# SCH_Smart_Door_Quach_Trung_an.net
KiCad netlist of a schematic drawn in Altium Designer
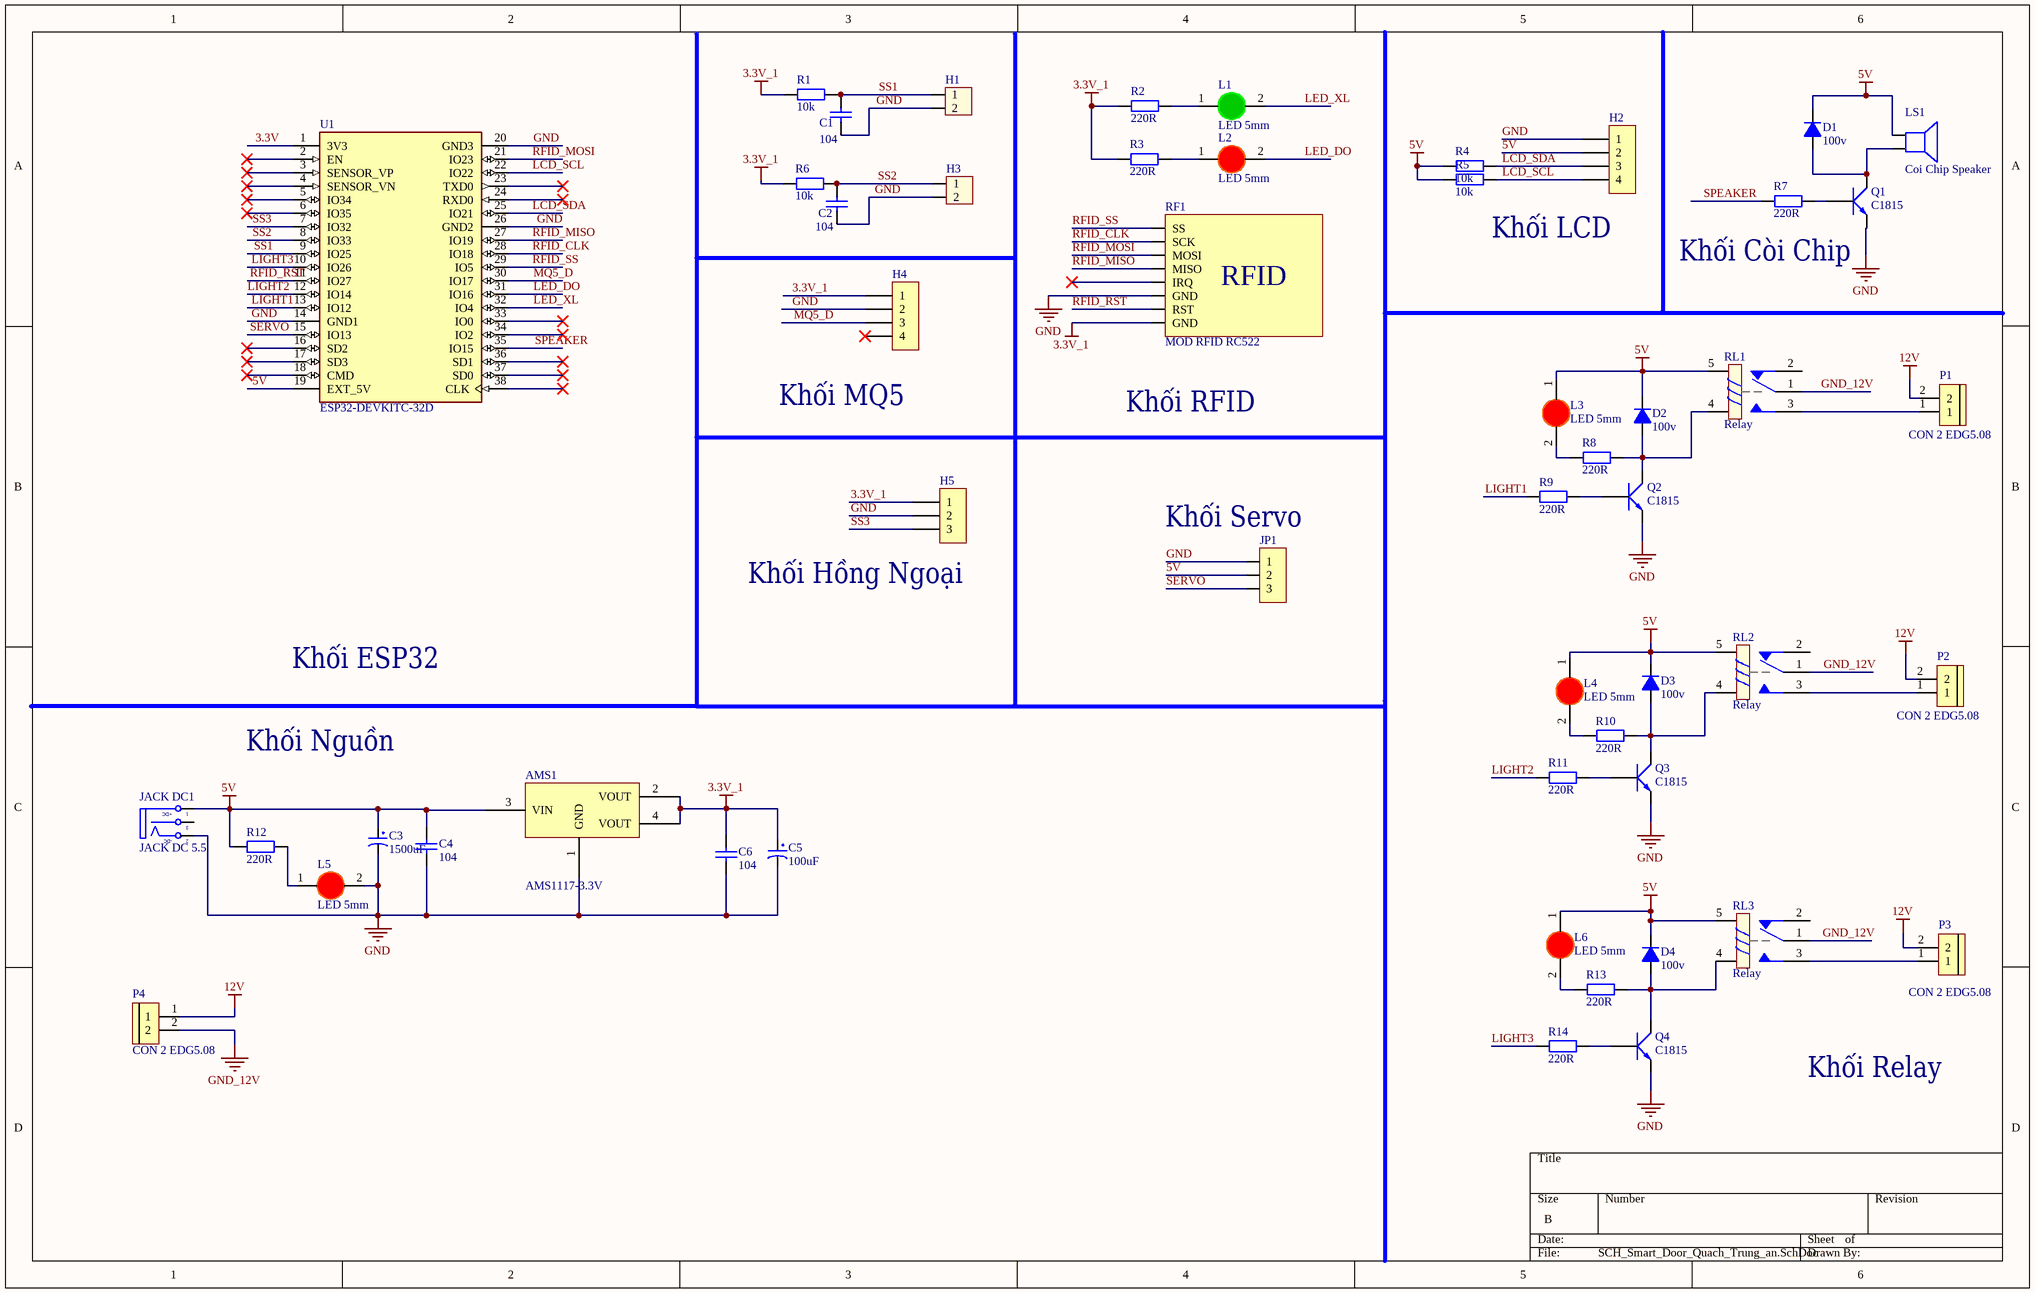
[diagram p0: SCH_Smart_Door_Quach_Trung_an.SchDoc]

(export (version "E")
  (design (tool "Eeschema 10.0.6"))
  (components
    (comp (ref "AMS1")
      (value "AMS1117-3.3V")
      (footprint "SOT223")
      (description "Dán")
      (libsource (lib "Altium_Lib_by_KhueNguyenCreator") (part "AMS1117 SMD"))
    )
    (comp (ref "C1")
      (value "104")
      (footprint "tu gom")
      (description "Cắm")
      (libsource (lib "Altium_Lib_by_KhueNguyenCreator") (part "Tu gom 104 50V"))
    )
    (comp (ref "C2")
      (value "104")
      (footprint "tu gom")
      (description "Cắm")
      (libsource (lib "Altium_Lib_by_KhueNguyenCreator") (part "Tu gom 104 50V"))
    )
    (comp (ref "C3")
      (value "1500uF")
      (footprint "tu hoa 10mm")
      (description "Cắm")
      (libsource (lib "Altium_Lib_by_KhueNguyenCreator") (part "Tu Hoa 1500uF 16V 10x20"))
    )
    (comp (ref "C4")
      (value "104")
      (footprint "tu gom")
      (description "Cắm")
      (libsource (lib "Altium_Lib_by_KhueNguyenCreator") (part "Tu gom 104 50V"))
    )
    (comp (ref "C5")
      (value "100uF")
      (footprint "tu hoa 5mm")
      (description "Cắm")
      (libsource (lib "Altium_Lib_by_KhueNguyenCreator") (part "Tu Hoa 100uF 16V 5x7"))
    )
    (comp (ref "C6")
      (value "104")
      (footprint "tu gom")
      (description "Cắm")
      (libsource (lib "Altium_Lib_by_KhueNguyenCreator") (part "Tu gom 104 50V"))
    )
    (comp (ref "D1")
      (value "100v")
      (footprint "DIODE 1A")
      (description "Cắm")
      (libsource (lib "Altium_Lib_by_KhueNguyenCreator") (part "Diode 1N4007"))
    )
    (comp (ref "D2")
      (value "100v")
      (footprint "DIODE 1A")
      (description "Cắm")
      (libsource (lib "Altium_Lib_by_KhueNguyenCreator") (part "Diode 1N4007"))
    )
    (comp (ref "D3")
      (value "100v")
      (footprint "DIODE 1A")
      (description "Cắm")
      (libsource (lib "Altium_Lib_by_KhueNguyenCreator") (part "Diode 1N4007"))
    )
    (comp (ref "D4")
      (value "100v")
      (footprint "DIODE 1A")
      (description "Cắm")
      (libsource (lib "Altium_Lib_by_KhueNguyenCreator") (part "Diode 1N4007"))
    )
    (comp (ref "H1")
      (value "Header 2P 2.54 Duc Cong")
      (footprint "Header 2P DC 2.54")
      (description "Cắm")
      (libsource (lib "Altium_Lib_by_KhueNguyenCreator") (part "Header 2P 2.54 Duc Cong"))
    )
    (comp (ref "H2")
      (value "Header 4P 2.54 Duc Cong")
      (footprint "Header 4P DC 2.54")
      (description "Cắm")
      (libsource (lib "Altium_Lib_by_KhueNguyenCreator") (part "Header 4P 2.54 Duc Cong"))
    )
    (comp (ref "H3")
      (value "Header 2P 2.54 Duc Cong")
      (footprint "Header 2P DC 2.54")
      (description "Cắm")
      (libsource (lib "Altium_Lib_by_KhueNguyenCreator") (part "Header 2P 2.54 Duc Cong"))
    )
    (comp (ref "H4")
      (value "Header 4P 2.54 Duc Cong")
      (footprint "Header 4P DC 2.54")
      (description "Cắm")
      (libsource (lib "Altium_Lib_by_KhueNguyenCreator") (part "Header 4P 2.54 Duc Cong"))
    )
    (comp (ref "H5")
      (value "Header 3P 2.54 Duc Cong")
      (footprint "Header 3P DC 2.54")
      (description "Cắm")
      (libsource (lib "Altium_Lib_by_KhueNguyenCreator") (part "Header 3P 2.54 Duc Cong"))
    )
    (comp (ref "JACK DC1")
      (value "JACK DC 5.5")
      (footprint "JACK DC 5.5")
      (libsource (lib "Altium_Lib_by_KhueNguyenCreator") (part "JACK DC 5.5"))
    )
    (comp (ref "JP1")
      (value "JP 1x3 2.54")
      (footprint "JP 1x3 DC")
      (description "Cắm")
      (libsource (lib "Altium_Lib_by_KhueNguyenCreator") (part "JP 1x3 2.54 Duc Cong"))
    )
    (comp (ref "L1")
      (value "LED 5mm")
      (footprint "LED-5MM-Green")
      (description "Cắm")
      (libsource (lib "Altium_Lib_by_KhueNguyenCreator") (part "LED 5mm Xanh La"))
    )
    (comp (ref "L2")
      (value "LED 5mm")
      (footprint "LED-5MM-RED")
      (description "Cắm")
      (libsource (lib "Altium_Lib_by_KhueNguyenCreator") (part "LED 5mm Do"))
    )
    (comp (ref "L3")
      (value "LED 5mm")
      (footprint "LED-5MM-RED")
      (description "Cắm")
      (libsource (lib "Altium_Lib_by_KhueNguyenCreator") (part "LED 5mm Do"))
    )
    (comp (ref "L4")
      (value "LED 5mm")
      (footprint "LED-5MM-RED")
      (description "Cắm")
      (libsource (lib "Altium_Lib_by_KhueNguyenCreator") (part "LED 5mm Do"))
    )
    (comp (ref "L5")
      (value "LED 5mm")
      (footprint "LED-5MM-RED")
      (description "Cắm")
      (libsource (lib "Altium_Lib_by_KhueNguyenCreator") (part "LED 5mm Do"))
    )
    (comp (ref "L6")
      (value "LED 5mm")
      (footprint "LED-5MM-RED")
      (description "Cắm")
      (libsource (lib "Altium_Lib_by_KhueNguyenCreator") (part "LED 5mm Do"))
    )
    (comp (ref "LS1")
      (value "Coi Chip Speaker")
      (footprint "Coi Chip Speacker")
      (description "Còi chip")
      (libsource (lib "Altium_Lib_by_KhueNguyenCreator") (part "Coi Chip Speaker"))
    )
    (comp (ref "P1")
      (value "CON 2 EDG5.08")
      (footprint "CON 2 2EDG5.08")
      (description "Cắm")
      (libsource (lib "Altium_Lib_by_KhueNguyenCreator") (part "CON 2 EDG5.08"))
    )
    (comp (ref "P2")
      (value "CON 2 EDG5.08")
      (footprint "CON 2 2EDG5.08")
      (description "Cắm")
      (libsource (lib "Altium_Lib_by_KhueNguyenCreator") (part "CON 2 EDG5.08"))
    )
    (comp (ref "P3")
      (value "CON 2 EDG5.08")
      (footprint "CON 2 2EDG5.08")
      (description "Cắm")
      (libsource (lib "Altium_Lib_by_KhueNguyenCreator") (part "CON 2 EDG5.08"))
    )
    (comp (ref "P4")
      (value "CON 2 EDG5.08")
      (footprint "CON 2 2EDG5.08")
      (description "Cắm")
      (libsource (lib "") (part "CON 2 EDG5.08_1"))
    )
    (comp (ref "Q1")
      (value "C1815")
      (footprint "TO92")
      (description "NPN transistor")
      (libsource (lib "Altium_Lib_by_KhueNguyenCreator") (part "C1815"))
    )
    (comp (ref "Q2")
      (value "C1815")
      (footprint "TO92")
      (description "NPN transistor")
      (libsource (lib "Altium_Lib_by_KhueNguyenCreator") (part "C1815"))
    )
    (comp (ref "Q3")
      (value "C1815")
      (footprint "TO92")
      (description "NPN transistor")
      (libsource (lib "Altium_Lib_by_KhueNguyenCreator") (part "C1815"))
    )
    (comp (ref "Q4")
      (value "C1815")
      (footprint "TO92")
      (description "NPN transistor")
      (libsource (lib "Altium_Lib_by_KhueNguyenCreator") (part "C1815"))
    )
    (comp (ref "R1")
      (value "10k")
      (footprint "tro vach 1/4w")
      (description "Căm")
      (libsource (lib "Altium_Lib_by_KhueNguyenCreator") (part "Tro Vach 1/4W 5% 10k"))
    )
    (comp (ref "R2")
      (value "220R")
      (footprint "tro vach 1/4w")
      (description "Cắm")
      (libsource (lib "Altium_Lib_by_KhueNguyenCreator") (part "Tro Vach 1/4W 5% 220R"))
    )
    (comp (ref "R3")
      (value "220R")
      (footprint "tro vach 1/4w")
      (description "Cắm")
      (libsource (lib "Altium_Lib_by_KhueNguyenCreator") (part "Tro Vach 1/4W 5% 220R"))
    )
    (comp (ref "R4")
      (value "10k")
      (footprint "tro vach 1/4w")
      (description "Căm")
      (libsource (lib "Altium_Lib_by_KhueNguyenCreator") (part "Tro Vach 1/4W 5% 10k"))
    )
    (comp (ref "R5")
      (value "10k")
      (footprint "tro vach 1/4w")
      (description "Căm")
      (libsource (lib "Altium_Lib_by_KhueNguyenCreator") (part "Tro Vach 1/4W 5% 10k"))
    )
    (comp (ref "R6")
      (value "10k")
      (footprint "tro vach 1/4w")
      (description "Căm")
      (libsource (lib "Altium_Lib_by_KhueNguyenCreator") (part "Tro Vach 1/4W 5% 10k"))
    )
    (comp (ref "R7")
      (value "220R")
      (footprint "tro vach 1/4w")
      (description "Cắm")
      (libsource (lib "Altium_Lib_by_KhueNguyenCreator") (part "Tro Vach 1/4W 5% 220R"))
    )
    (comp (ref "R8")
      (value "220R")
      (footprint "tro vach 1/4w")
      (description "Cắm")
      (libsource (lib "Altium_Lib_by_KhueNguyenCreator") (part "Tro Vach 1/4W 5% 220R"))
    )
    (comp (ref "R9")
      (value "220R")
      (footprint "tro vach 1/4w")
      (description "Cắm")
      (libsource (lib "Altium_Lib_by_KhueNguyenCreator") (part "Tro Vach 1/4W 5% 220R"))
    )
    (comp (ref "R10")
      (value "220R")
      (footprint "tro vach 1/4w")
      (description "Cắm")
      (libsource (lib "Altium_Lib_by_KhueNguyenCreator") (part "Tro Vach 1/4W 5% 220R"))
    )
    (comp (ref "R11")
      (value "220R")
      (footprint "tro vach 1/4w")
      (description "Cắm")
      (libsource (lib "Altium_Lib_by_KhueNguyenCreator") (part "Tro Vach 1/4W 5% 220R"))
    )
    (comp (ref "R12")
      (value "220R")
      (footprint "tro vach 1/4w")
      (description "Cắm")
      (libsource (lib "Altium_Lib_by_KhueNguyenCreator") (part "Tro Vach 1/4W 5% 220R"))
    )
    (comp (ref "R13")
      (value "220R")
      (footprint "tro vach 1/4w")
      (description "Cắm")
      (libsource (lib "Altium_Lib_by_KhueNguyenCreator") (part "Tro Vach 1/4W 5% 220R"))
    )
    (comp (ref "R14")
      (value "220R")
      (footprint "tro vach 1/4w")
      (description "Cắm")
      (libsource (lib "Altium_Lib_by_KhueNguyenCreator") (part "Tro Vach 1/4W 5% 220R"))
    )
    (comp (ref "RF1")
      (value "MOD RFID RC522")
      (footprint "MOD RFID RC522")
      (libsource (lib "Altium_Lib_by_KhueNguyenCreator") (part "MOD RFID RC522"))
    )
    (comp (ref "RL1")
      (value "Relay")
      (footprint "Relay 5 Chan SRD")
      (description "Relay 5 Chan")
      (libsource (lib "Altium_Lib_by_KhueNguyenCreator") (part "Relay 5 Chan SRD"))
    )
    (comp (ref "RL2")
      (value "Relay")
      (footprint "Relay 5 Chan SRD")
      (description "Relay 5 Chan")
      (libsource (lib "Altium_Lib_by_KhueNguyenCreator") (part "Relay 5 Chan SRD"))
    )
    (comp (ref "RL3")
      (value "Relay")
      (footprint "Relay 5 Chan SRD")
      (description "Relay 5 Chan")
      (libsource (lib "Altium_Lib_by_KhueNguyenCreator") (part "Relay 5 Chan SRD"))
    )
    (comp (ref "U1")
      (value "ESP32-DEVKITC-32D")
      (footprint "MODULE_ESP32-DEVKITC-32D")
      (description "EVAL BOARD FOR ESP-WROOM-32")
      (fields (field (name "MF") "Espressif Systems"))
      (libsource (lib "Altium_Lib_by_KhueNguyenCreator") (part "ESP32-DEVKITC-32D"))
    )
  )
  (nets
    (net (code "1") (name "/3.3V") (class "Default")
      (node (ref "U1") (pin "1") (pinfunction "3V3_1") (pintype "power_in"))
    )
    (net (code "2") (name "/LCD_SCL") (class "Default")
      (node (ref "H2") (pin "4") (pinfunction "4_4") (pintype "passive"))
      (node (ref "R5") (pin "2") (pinfunction "2_2") (pintype "passive"))
      (node (ref "U1") (pin "22") (pinfunction "IO22_22") (pintype "bidirectional"))
    )
    (net (code "3") (name "/LCD_SDA") (class "Default")
      (node (ref "H2") (pin "3") (pinfunction "3_3") (pintype "passive"))
      (node (ref "R4") (pin "2") (pinfunction "2_2") (pintype "passive"))
      (node (ref "U1") (pin "25") (pinfunction "IO21_25") (pintype "bidirectional"))
    )
    (net (code "4") (name "/LED_DO") (class "Default")
      (node (ref "L2") (pin "2") (pinfunction "K_2") (pintype "passive"))
      (node (ref "U1") (pin "31") (pinfunction "IO16_31") (pintype "bidirectional"))
    )
    (net (code "5") (name "/LED_XL") (class "Default")
      (node (ref "L1") (pin "2") (pinfunction "K_2") (pintype "passive"))
      (node (ref "U1") (pin "32") (pinfunction "IO4_32") (pintype "bidirectional"))
    )
    (net (code "6") (name "/LIGHT1") (class "Default")
      (node (ref "R9") (pin "1") (pinfunction "1_1") (pintype "passive"))
      (node (ref "U1") (pin "13") (pinfunction "IO12_13") (pintype "bidirectional"))
    )
    (net (code "7") (name "/LIGHT2") (class "Default")
      (node (ref "R11") (pin "1") (pinfunction "1_1") (pintype "passive"))
      (node (ref "U1") (pin "12") (pinfunction "IO14_12") (pintype "bidirectional"))
    )
    (net (code "8") (name "/LIGHT3") (class "Default")
      (node (ref "R14") (pin "1") (pinfunction "1_1") (pintype "passive"))
      (node (ref "U1") (pin "10") (pinfunction "IO26_10") (pintype "bidirectional"))
    )
    (net (code "9") (name "/MQ5_D") (class "Default")
      (node (ref "H4") (pin "3") (pinfunction "3_3") (pintype "passive"))
      (node (ref "U1") (pin "30") (pinfunction "IO17_30") (pintype "bidirectional"))
    )
    (net (code "10") (name "/RFID_CLK") (class "Default")
      (node (ref "RF1") (pin "2") (pinfunction "SCK_2") (pintype "passive"))
      (node (ref "U1") (pin "28") (pinfunction "IO18_28") (pintype "bidirectional"))
    )
    (net (code "11") (name "/RFID_MISO") (class "Default")
      (node (ref "RF1") (pin "4") (pinfunction "MISO_4") (pintype "passive"))
      (node (ref "U1") (pin "27") (pinfunction "IO19_27") (pintype "bidirectional"))
    )
    (net (code "12") (name "/RFID_MOSI") (class "Default")
      (node (ref "RF1") (pin "3") (pinfunction "MOSI_3") (pintype "passive"))
      (node (ref "U1") (pin "21") (pinfunction "IO23_21") (pintype "bidirectional"))
    )
    (net (code "13") (name "/RFID_RST") (class "Default")
      (node (ref "RF1") (pin "7") (pinfunction "RST_7") (pintype "passive"))
      (node (ref "U1") (pin "11") (pinfunction "IO27_11") (pintype "bidirectional"))
    )
    (net (code "14") (name "/RFID_SS") (class "Default")
      (node (ref "RF1") (pin "1") (pinfunction "SS_1") (pintype "passive"))
      (node (ref "U1") (pin "29") (pinfunction "IO5_29") (pintype "bidirectional"))
    )
    (net (code "15") (name "/SERVO") (class "Default")
      (node (ref "JP1") (pin "3") (pinfunction "3_3") (pintype "passive"))
      (node (ref "U1") (pin "15") (pinfunction "IO13_15") (pintype "bidirectional"))
    )
    (net (code "16") (name "/SPEAKER") (class "Default")
      (node (ref "R7") (pin "1") (pinfunction "1_1") (pintype "passive"))
      (node (ref "U1") (pin "35") (pinfunction "IO15_35") (pintype "bidirectional"))
    )
    (net (code "17") (name "/SS1") (class "Default")
      (node (ref "C1") (pin "1") (pinfunction "1_1") (pintype "passive"))
      (node (ref "H1") (pin "1") (pinfunction "1_1") (pintype "passive"))
      (node (ref "R1") (pin "2") (pinfunction "2_2") (pintype "passive"))
      (node (ref "U1") (pin "9") (pinfunction "IO25_9") (pintype "bidirectional"))
    )
    (net (code "18") (name "/SS2") (class "Default")
      (node (ref "C2") (pin "1") (pinfunction "1_1") (pintype "passive"))
      (node (ref "H3") (pin "1") (pinfunction "1_1") (pintype "passive"))
      (node (ref "R6") (pin "2") (pinfunction "2_2") (pintype "passive"))
      (node (ref "U1") (pin "8") (pinfunction "IO33_8") (pintype "bidirectional"))
    )
    (net (code "19") (name "/SS3") (class "Default")
      (node (ref "H5") (pin "3") (pinfunction "3_3") (pintype "passive"))
      (node (ref "U1") (pin "7") (pinfunction "IO32_7") (pintype "bidirectional"))
    )
    (net (code "20") (name "3.3V_1") (class "Default")
      (node (ref "AMS1") (pin "2") (pinfunction "VOUT_2") (pintype "passive"))
      (node (ref "AMS1") (pin "4") (pinfunction "VOUT_4") (pintype "passive"))
      (node (ref "C5") (pin "1") (pinfunction "1_1") (pintype "passive"))
      (node (ref "C6") (pin "1") (pinfunction "1_1") (pintype "passive"))
      (node (ref "H4") (pin "1") (pinfunction "1_1") (pintype "passive"))
      (node (ref "H5") (pin "1") (pinfunction "1_1") (pintype "passive"))
      (node (ref "R1") (pin "1") (pinfunction "1_1") (pintype "passive"))
      (node (ref "R2") (pin "1") (pinfunction "1_1") (pintype "passive"))
      (node (ref "R3") (pin "1") (pinfunction "1_1") (pintype "passive"))
      (node (ref "R6") (pin "1") (pinfunction "1_1") (pintype "passive"))
      (node (ref "RF1") (pin "8") (pinfunction "GND_8") (pintype "passive"))
    )
    (net (code "21") (name "5V") (class "Default")
      (node (ref "AMS1") (pin "3") (pinfunction "VIN_3") (pintype "passive"))
      (node (ref "C3") (pin "1") (pinfunction "1_1") (pintype "passive"))
      (node (ref "C4") (pin "1") (pinfunction "1_1") (pintype "passive"))
      (node (ref "D1") (pin "2") (pinfunction "K_2") (pintype "passive"))
      (node (ref "D2") (pin "2") (pinfunction "K_2") (pintype "passive"))
      (node (ref "D3") (pin "2") (pinfunction "K_2") (pintype "passive"))
      (node (ref "D4") (pin "2") (pinfunction "K_2") (pintype "passive"))
      (node (ref "H2") (pin "2") (pinfunction "2_2") (pintype "passive"))
      (node (ref "JACK DC1") (pin "1") (pinfunction "T_1") (pintype "passive"))
      (node (ref "JP1") (pin "2") (pinfunction "2_2") (pintype "passive"))
      (node (ref "L3") (pin "1") (pinfunction "A_1") (pintype "passive"))
      (node (ref "L4") (pin "1") (pinfunction "A_1") (pintype "passive"))
      (node (ref "L6") (pin "1") (pinfunction "A_1") (pintype "passive"))
      (node (ref "LS1") (pin "1") (pinfunction "1_1") (pintype "passive"))
      (node (ref "R12") (pin "1") (pinfunction "1_1") (pintype "passive"))
      (node (ref "R4") (pin "1") (pinfunction "1_1") (pintype "passive"))
      (node (ref "R5") (pin "1") (pinfunction "1_1") (pintype "passive"))
      (node (ref "RL1") (pin "5") (pinfunction "5_5") (pintype "passive"))
      (node (ref "RL2") (pin "5") (pinfunction "5_5") (pintype "passive"))
      (node (ref "RL3") (pin "5") (pinfunction "5_5") (pintype "passive"))
      (node (ref "U1") (pin "19") (pinfunction "EXT_5V_19") (pintype "power_in"))
    )
    (net (code "22") (name "12V") (class "Default")
      (node (ref "P1") (pin "2") (pinfunction "2_2") (pintype "passive"))
      (node (ref "P2") (pin "2") (pinfunction "2_2") (pintype "passive"))
      (node (ref "P3") (pin "2") (pinfunction "2_2") (pintype "passive"))
      (node (ref "P4") (pin "1") (pinfunction "1_1") (pintype "passive"))
    )
    (net (code "23") (name "GND") (class "Default")
      (node (ref "AMS1") (pin "1") (pinfunction "GND_1") (pintype "passive"))
      (node (ref "C1") (pin "2") (pinfunction "2_2") (pintype "passive"))
      (node (ref "C2") (pin "2") (pinfunction "2_2") (pintype "passive"))
      (node (ref "C3") (pin "2") (pinfunction "2_2") (pintype "passive"))
      (node (ref "C4") (pin "2") (pinfunction "2_2") (pintype "passive"))
      (node (ref "C5") (pin "2") (pinfunction "2_2") (pintype "passive"))
      (node (ref "C6") (pin "2") (pinfunction "2_2") (pintype "passive"))
      (node (ref "H1") (pin "2") (pinfunction "2_2") (pintype "passive"))
      (node (ref "H2") (pin "1") (pinfunction "1_1") (pintype "passive"))
      (node (ref "H3") (pin "2") (pinfunction "2_2") (pintype "passive"))
      (node (ref "H4") (pin "2") (pinfunction "2_2") (pintype "passive"))
      (node (ref "H5") (pin "2") (pinfunction "2_2") (pintype "passive"))
      (node (ref "JACK DC1") (pin "2") (pinfunction "TN_2") (pintype "passive"))
      (node (ref "JP1") (pin "1") (pinfunction "1_1") (pintype "passive"))
      (node (ref "L5") (pin "2") (pinfunction "K_2") (pintype "passive"))
      (node (ref "Q1") (pin "1") (pinfunction "E_1") (pintype "passive"))
      (node (ref "Q2") (pin "1") (pinfunction "E_1") (pintype "passive"))
      (node (ref "Q3") (pin "1") (pinfunction "E_1") (pintype "passive"))
      (node (ref "Q4") (pin "1") (pinfunction "E_1") (pintype "passive"))
      (node (ref "RF1") (pin "6") (pinfunction "GND_6") (pintype "passive"))
      (node (ref "U1") (pin "14") (pinfunction "GND1_14") (pintype "power_in"))
      (node (ref "U1") (pin "20") (pinfunction "GND3_20") (pintype "power_in"))
      (node (ref "U1") (pin "26") (pinfunction "GND2_26") (pintype "power_in"))
    )
    (net (code "24") (name "GND_12V") (class "Default")
      (node (ref "P4") (pin "2") (pinfunction "2_2") (pintype "passive"))
      (node (ref "RL1") (pin "1") (pinfunction "1_1") (pintype "passive"))
      (node (ref "RL2") (pin "1") (pinfunction "1_1") (pintype "passive"))
      (node (ref "RL3") (pin "1") (pinfunction "1_1") (pintype "passive"))
    )
    (net (code "25") (name "Net-(D1-A)") (class "Default")
      (node (ref "D1") (pin "1") (pinfunction "A_1") (pintype "passive"))
      (node (ref "LS1") (pin "2") (pinfunction "2_2") (pintype "passive"))
      (node (ref "Q1") (pin "2") (pinfunction "C_2") (pintype "passive"))
    )
    (net (code "26") (name "Net-(D2-A)") (class "Default")
      (node (ref "D2") (pin "1") (pinfunction "A_1") (pintype "passive"))
      (node (ref "Q2") (pin "2") (pinfunction "C_2") (pintype "passive"))
      (node (ref "R8") (pin "1") (pinfunction "1_1") (pintype "passive"))
      (node (ref "RL1") (pin "4") (pinfunction "4_4") (pintype "passive"))
    )
    (net (code "27") (name "Net-(D3-A)") (class "Default")
      (node (ref "D3") (pin "1") (pinfunction "A_1") (pintype "passive"))
      (node (ref "Q3") (pin "2") (pinfunction "C_2") (pintype "passive"))
      (node (ref "R10") (pin "1") (pinfunction "1_1") (pintype "passive"))
      (node (ref "RL2") (pin "4") (pinfunction "4_4") (pintype "passive"))
    )
    (net (code "28") (name "Net-(D4-A)") (class "Default")
      (node (ref "D4") (pin "1") (pinfunction "A_1") (pintype "passive"))
      (node (ref "Q4") (pin "2") (pinfunction "C_2") (pintype "passive"))
      (node (ref "R13") (pin "1") (pinfunction "1_1") (pintype "passive"))
      (node (ref "RL3") (pin "4") (pinfunction "4_4") (pintype "passive"))
    )
    (net (code "29") (name "Net-(L1-A)") (class "Default")
      (node (ref "L1") (pin "1") (pinfunction "A_1") (pintype "passive"))
      (node (ref "R2") (pin "2") (pinfunction "2_2") (pintype "passive"))
    )
    (net (code "30") (name "Net-(L2-A)") (class "Default")
      (node (ref "L2") (pin "1") (pinfunction "A_1") (pintype "passive"))
      (node (ref "R3") (pin "2") (pinfunction "2_2") (pintype "passive"))
    )
    (net (code "31") (name "Net-(L3-K)") (class "Default")
      (node (ref "L3") (pin "2") (pinfunction "K_2") (pintype "passive"))
      (node (ref "R8") (pin "2") (pinfunction "2_2") (pintype "passive"))
    )
    (net (code "32") (name "Net-(L4-K)") (class "Default")
      (node (ref "L4") (pin "2") (pinfunction "K_2") (pintype "passive"))
      (node (ref "R10") (pin "2") (pinfunction "2_2") (pintype "passive"))
    )
    (net (code "33") (name "Net-(L5-A)") (class "Default")
      (node (ref "L5") (pin "1") (pinfunction "A_1") (pintype "passive"))
      (node (ref "R12") (pin "2") (pinfunction "2_2") (pintype "passive"))
    )
    (net (code "34") (name "Net-(L6-K)") (class "Default")
      (node (ref "L6") (pin "2") (pinfunction "K_2") (pintype "passive"))
      (node (ref "R13") (pin "2") (pinfunction "2_2") (pintype "passive"))
    )
    (net (code "35") (name "Net-(P1-Pad1)") (class "Default")
      (node (ref "P1") (pin "1") (pinfunction "1_1") (pintype "passive"))
      (node (ref "RL1") (pin "3") (pinfunction "3_3") (pintype "passive"))
    )
    (net (code "36") (name "Net-(P2-Pad1)") (class "Default")
      (node (ref "P2") (pin "1") (pinfunction "1_1") (pintype "passive"))
      (node (ref "RL2") (pin "3") (pinfunction "3_3") (pintype "passive"))
    )
    (net (code "37") (name "Net-(P3-Pad1)") (class "Default")
      (node (ref "P3") (pin "1") (pinfunction "1_1") (pintype "passive"))
      (node (ref "RL3") (pin "3") (pinfunction "3_3") (pintype "passive"))
    )
    (net (code "38") (name "Net-(Q1-B)") (class "Default")
      (node (ref "Q1") (pin "3") (pinfunction "B_3") (pintype "passive"))
      (node (ref "R7") (pin "2") (pinfunction "2_2") (pintype "passive"))
    )
    (net (code "39") (name "Net-(Q2-B)") (class "Default")
      (node (ref "Q2") (pin "3") (pinfunction "B_3") (pintype "passive"))
      (node (ref "R9") (pin "2") (pinfunction "2_2") (pintype "passive"))
    )
    (net (code "40") (name "Net-(Q3-B)") (class "Default")
      (node (ref "Q3") (pin "3") (pinfunction "B_3") (pintype "passive"))
      (node (ref "R11") (pin "2") (pinfunction "2_2") (pintype "passive"))
    )
    (net (code "41") (name "Net-(Q4-B)") (class "Default")
      (node (ref "Q4") (pin "3") (pinfunction "B_3") (pintype "passive"))
      (node (ref "R14") (pin "2") (pinfunction "2_2") (pintype "passive"))
    )
    (net (code "42") (name "unconnected-(H4-Pad4)") (class "Default")
      (node (ref "H4") (pin "4") (pinfunction "4_4") (pintype "passive+no_connect"))
    )
    (net (code "43") (name "unconnected-(JACK DC1-S-Pad3)") (class "Default")
      (node (ref "JACK DC1") (pin "3") (pinfunction "S_3") (pintype "power_in"))
    )
    (net (code "44") (name "unconnected-(RF1-IRQ-Pad5)") (class "Default")
      (node (ref "RF1") (pin "5") (pinfunction "IRQ_5") (pintype "passive+no_connect"))
    )
    (net (code "45") (name "unconnected-(RL1-Pad2)") (class "Default")
      (node (ref "RL1") (pin "2") (pinfunction "2_2") (pintype "passive"))
    )
    (net (code "46") (name "unconnected-(RL2-Pad2)") (class "Default")
      (node (ref "RL2") (pin "2") (pinfunction "2_2") (pintype "passive"))
    )
    (net (code "47") (name "unconnected-(RL3-Pad2)") (class "Default")
      (node (ref "RL3") (pin "2") (pinfunction "2_2") (pintype "passive"))
    )
    (net (code "48") (name "unconnected-(U1-CLK-Pad38)") (class "Default")
      (node (ref "U1") (pin "38") (pinfunction "CLK_38") (pintype "input+no_connect"))
    )
    (net (code "49") (name "unconnected-(U1-CMD-Pad18)") (class "Default")
      (node (ref "U1") (pin "18") (pinfunction "CMD_18") (pintype "bidirectional+no_connect"))
    )
    (net (code "50") (name "unconnected-(U1-EN-Pad2)") (class "Default")
      (node (ref "U1") (pin "2") (pinfunction "EN_2") (pintype "input+no_connect"))
    )
    (net (code "51") (name "unconnected-(U1-IO0-Pad33)") (class "Default")
      (node (ref "U1") (pin "33") (pinfunction "IO0_33") (pintype "bidirectional+no_connect"))
    )
    (net (code "52") (name "unconnected-(U1-IO2-Pad34)") (class "Default")
      (node (ref "U1") (pin "34") (pinfunction "IO2_34") (pintype "bidirectional+no_connect"))
    )
    (net (code "53") (name "unconnected-(U1-IO34-Pad5)") (class "Default")
      (node (ref "U1") (pin "5") (pinfunction "IO34_5") (pintype "bidirectional+no_connect"))
    )
    (net (code "54") (name "unconnected-(U1-IO35-Pad6)") (class "Default")
      (node (ref "U1") (pin "6") (pinfunction "IO35_6") (pintype "bidirectional+no_connect"))
    )
    (net (code "55") (name "unconnected-(U1-RXD0-Pad24)") (class "Default")
      (node (ref "U1") (pin "24") (pinfunction "RXD0_24") (pintype "input+no_connect"))
    )
    (net (code "56") (name "unconnected-(U1-SD0-Pad37)") (class "Default")
      (node (ref "U1") (pin "37") (pinfunction "SD0_37") (pintype "bidirectional+no_connect"))
    )
    (net (code "57") (name "unconnected-(U1-SD1-Pad36)") (class "Default")
      (node (ref "U1") (pin "36") (pinfunction "SD1_36") (pintype "bidirectional+no_connect"))
    )
    (net (code "58") (name "unconnected-(U1-SD2-Pad16)") (class "Default")
      (node (ref "U1") (pin "16") (pinfunction "SD2_16") (pintype "bidirectional+no_connect"))
    )
    (net (code "59") (name "unconnected-(U1-SD3-Pad17)") (class "Default")
      (node (ref "U1") (pin "17") (pinfunction "SD3_17") (pintype "bidirectional+no_connect"))
    )
    (net (code "60") (name "unconnected-(U1-SENSOR_VN-Pad4)") (class "Default")
      (node (ref "U1") (pin "4") (pinfunction "SENSOR_VN_4") (pintype "input+no_connect"))
    )
    (net (code "61") (name "unconnected-(U1-SENSOR_VP-Pad3)") (class "Default")
      (node (ref "U1") (pin "3") (pinfunction "SENSOR_VP_3") (pintype "input+no_connect"))
    )
    (net (code "62") (name "unconnected-(U1-TXD0-Pad23)") (class "Default")
      (node (ref "U1") (pin "23") (pinfunction "TXD0_23") (pintype "output+no_connect"))
    )
  )
)
